# Fortuna-v21.net
KiCad netlist of a schematic drawn in EAGLE
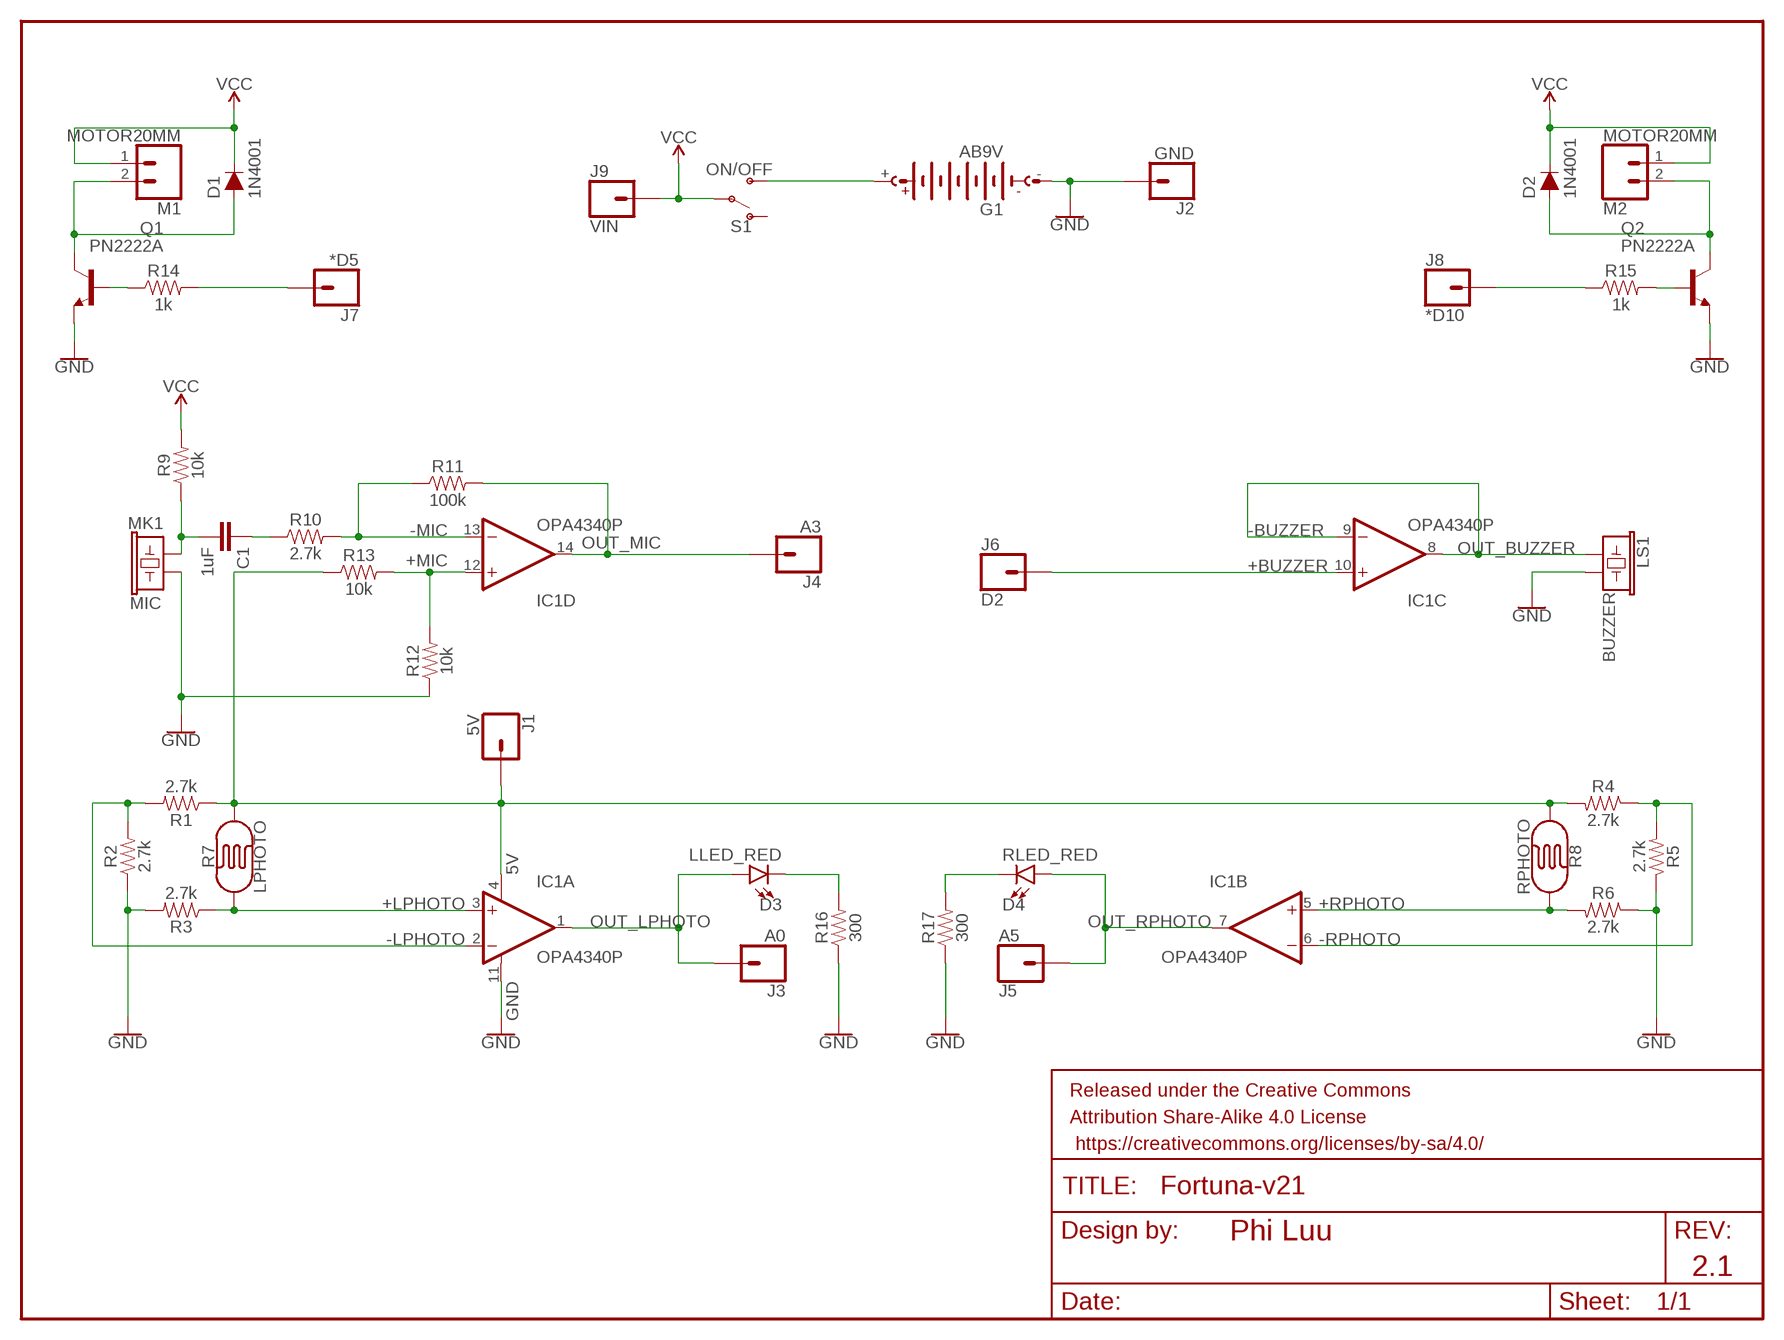
[diagram p0: schematic, sheet 1]

(export (version "E")
  (design (tool "Eeschema 10.0.6"))
  (components
    (comp (ref "C1")
      (value "1uF")
      (footprint "eagle-import:CAP-PTH-SMALL-KIT")
      (libsource (lib "eagle-import") (part "0.1UF-KIT-EZ-50V-20%"))
    )
    (comp (ref "D1")
      (value "1N4001")
      (footprint "eagle-import:DIODE-1N4001")
      (libsource (lib "eagle-import") (part "DIODE-PTH"))
    )
    (comp (ref "D2")
      (value "1N4001")
      (footprint "eagle-import:DIODE-1N4001")
      (libsource (lib "eagle-import") (part "DIODE-PTH"))
    )
    (comp (ref "D3")
      (value "LLED_RED")
      (footprint "eagle-import:LED_5MM")
      (libsource (lib "eagle-import") (part "LED5MM"))
    )
    (comp (ref "D4")
      (value "RLED_RED")
      (footprint "eagle-import:LED_5MM")
      (libsource (lib "eagle-import") (part "LED5MM"))
    )
    (comp (ref "FRAME1")
      (value "FRAME-LETTER")
      (footprint "eagle-import:CREATIVE_COMMONS")
      (libsource (lib "eagle-import") (part "FRAME-LETTER"))
    )
    (comp (ref "G1")
      (value "AB9V")
      (footprint "eagle-import:AB9V")
      (libsource (lib "eagle-import") (part "AB9V"))
    )
    (comp (ref "IC1")
      (value "OPA4340P")
      (footprint "eagle-import:DIL14")
      (libsource (lib "eagle-import") (part "OPA4340P"))
    )
    (comp (ref "J1")
      (value "5V")
      (footprint "eagle-import:1X01")
      (libsource (lib "eagle-import") (part "CONN_01"))
    )
    (comp (ref "J2")
      (value "GND")
      (footprint "eagle-import:1X01")
      (libsource (lib "eagle-import") (part "CONN_01"))
    )
    (comp (ref "J3")
      (value "A0")
      (footprint "eagle-import:1X01")
      (libsource (lib "eagle-import") (part "CONN_01"))
    )
    (comp (ref "J4")
      (value "A3")
      (footprint "eagle-import:1X01")
      (libsource (lib "eagle-import") (part "CONN_01"))
    )
    (comp (ref "J5")
      (value "A5")
      (footprint "eagle-import:1X01")
      (libsource (lib "eagle-import") (part "CONN_01"))
    )
    (comp (ref "J6")
      (value "D2")
      (footprint "eagle-import:1X01")
      (libsource (lib "eagle-import") (part "CONN_01"))
    )
    (comp (ref "J7")
      (value "*D5")
      (footprint "eagle-import:1X01")
      (libsource (lib "eagle-import") (part "CONN_01"))
    )
    (comp (ref "J8")
      (value "*D10")
      (footprint "eagle-import:1X01")
      (libsource (lib "eagle-import") (part "CONN_01"))
    )
    (comp (ref "J9")
      (value "VIN")
      (footprint "eagle-import:1X01")
      (libsource (lib "eagle-import") (part "CONN_01"))
    )
    (comp (ref "LS1")
      (value "BUZZER")
      (footprint "eagle-import:BUZZER-12MM")
      (libsource (lib "eagle-import") (part "BUZZER-PTH"))
    )
    (comp (ref "M1")
      (value "MOTOR20MM")
      (footprint "eagle-import:1X02")
      (libsource (lib "eagle-import") (part "CONN_02"))
    )
    (comp (ref "M2")
      (value "MOTOR20MM")
      (footprint "eagle-import:1X02")
      (libsource (lib "eagle-import") (part "CONN_02"))
    )
    (comp (ref "MK1")
      (value "MIC")
      (footprint "eagle-import:MICROPHONE-PTH-9.7MM")
      (libsource (lib "eagle-import") (part "MIC-PTH"))
    )
    (comp (ref "Q1")
      (value "PN2222A")
      (footprint "eagle-import:TO92-EBC-OVAL")
      (libsource (lib "eagle-import") (part "2N2222"))
    )
    (comp (ref "Q2")
      (value "PN2222A")
      (footprint "eagle-import:TO92-EBC-OVAL")
      (libsource (lib "eagle-import") (part "2N2222"))
    )
    (comp (ref "R1")
      (value "2.7k")
      (footprint "eagle-import:AXIAL-0.3")
      (libsource (lib "eagle-import") (part "1KOHM-HORIZ-1/4W-5%"))
    )
    (comp (ref "R2")
      (value "2.7k")
      (footprint "eagle-import:AXIAL-0.3")
      (libsource (lib "eagle-import") (part "1KOHM-HORIZ-1/4W-5%"))
    )
    (comp (ref "R3")
      (value "2.7k")
      (footprint "eagle-import:AXIAL-0.3")
      (libsource (lib "eagle-import") (part "1KOHM-HORIZ-1/4W-5%"))
    )
    (comp (ref "R4")
      (value "2.7k")
      (footprint "eagle-import:AXIAL-0.3")
      (libsource (lib "eagle-import") (part "1KOHM-HORIZ-1/4W-5%"))
    )
    (comp (ref "R5")
      (value "2.7k")
      (footprint "eagle-import:AXIAL-0.3")
      (libsource (lib "eagle-import") (part "1KOHM-HORIZ-1/4W-5%"))
    )
    (comp (ref "R6")
      (value "2.7k")
      (footprint "eagle-import:AXIAL-0.3")
      (libsource (lib "eagle-import") (part "1KOHM-HORIZ-1/4W-5%"))
    )
    (comp (ref "R7")
      (value "LPHOTO")
      (footprint "eagle-import:PHOTOCELL")
      (libsource (lib "eagle-import") (part "PHOTOCELLPTH"))
    )
    (comp (ref "R8")
      (value "RPHOTO")
      (footprint "eagle-import:PHOTOCELL")
      (libsource (lib "eagle-import") (part "PHOTOCELLPTH"))
    )
    (comp (ref "R9")
      (value "10k")
      (footprint "eagle-import:AXIAL-0.3")
      (libsource (lib "eagle-import") (part "1KOHM-HORIZ-1/4W-5%"))
    )
    (comp (ref "R10")
      (value "2.7k")
      (footprint "eagle-import:AXIAL-0.3")
      (libsource (lib "eagle-import") (part "1KOHM-HORIZ-1/4W-5%"))
    )
    (comp (ref "R11")
      (value "100k")
      (footprint "eagle-import:AXIAL-0.3")
      (libsource (lib "eagle-import") (part "1KOHM-HORIZ-1/4W-5%"))
    )
    (comp (ref "R12")
      (value "10k")
      (footprint "eagle-import:AXIAL-0.3")
      (libsource (lib "eagle-import") (part "1KOHM-HORIZ-1/4W-5%"))
    )
    (comp (ref "R13")
      (value "10k")
      (footprint "eagle-import:AXIAL-0.3")
      (libsource (lib "eagle-import") (part "1KOHM-HORIZ-1/4W-5%"))
    )
    (comp (ref "R14")
      (value "1k")
      (footprint "eagle-import:AXIAL-0.3")
      (libsource (lib "eagle-import") (part "1KOHM-HORIZ-1/4W-5%"))
    )
    (comp (ref "R15")
      (value "1k")
      (footprint "eagle-import:AXIAL-0.3")
      (libsource (lib "eagle-import") (part "1KOHM-HORIZ-1/4W-5%"))
    )
    (comp (ref "R16")
      (value "300")
      (footprint "eagle-import:AXIAL-0.3")
      (libsource (lib "eagle-import") (part "1KOHM-HORIZ-1/4W-5%"))
    )
    (comp (ref "R17")
      (value "300")
      (footprint "eagle-import:AXIAL-0.3")
      (libsource (lib "eagle-import") (part "1KOHM-HORIZ-1/4W-5%"))
    )
    (comp (ref "S1")
      (value "ON/OFF")
      (footprint "eagle-import:SWITCH_SPDT_PTH_11.6X4.0MM")
      (libsource (lib "eagle-import") (part "SWITCH-SPDT-PTH-11.6X4.0MM"))
    )
  )
  (nets
    (net (code "1") (name "/+LPHOTO") (class "Default")
      (node (ref "IC1") (pin "3") (pinfunction "+IN_3") (pintype "input"))
      (node (ref "R3") (pin "P$1") (pinfunction "1_P$1") (pintype "passive"))
      (node (ref "R7") (pin "1") (pinfunction "P$1_1") (pintype "bidirectional"))
    )
    (net (code "2") (name "/+MIC") (class "Default")
      (node (ref "IC1") (pin "12") (pinfunction "+IN_12") (pintype "input"))
      (node (ref "R12") (pin "P$2") (pinfunction "2_P$2") (pintype "passive"))
      (node (ref "R13") (pin "P$2") (pinfunction "2_P$2") (pintype "passive"))
    )
    (net (code "3") (name "/+RPHOTO") (class "Default")
      (node (ref "IC1") (pin "5") (pinfunction "+IN_5") (pintype "input"))
      (node (ref "R6") (pin "P$2") (pinfunction "2_P$2") (pintype "passive"))
      (node (ref "R8") (pin "1") (pinfunction "P$1_1") (pintype "bidirectional"))
    )
    (net (code "4") (name "/-LPHOTO") (class "Default")
      (node (ref "IC1") (pin "2") (pinfunction "-IN_2") (pintype "input"))
      (node (ref "R1") (pin "P$2") (pinfunction "2_P$2") (pintype "passive"))
      (node (ref "R2") (pin "P$2") (pinfunction "2_P$2") (pintype "passive"))
    )
    (net (code "5") (name "/-MIC") (class "Default")
      (node (ref "IC1") (pin "13") (pinfunction "-IN_13") (pintype "input"))
      (node (ref "R10") (pin "P$2") (pinfunction "2_P$2") (pintype "passive"))
      (node (ref "R11") (pin "P$1") (pinfunction "1_P$1") (pintype "passive"))
    )
    (net (code "6") (name "/-RPHOTO") (class "Default")
      (node (ref "IC1") (pin "6") (pinfunction "-IN_6") (pintype "input"))
      (node (ref "R4") (pin "P$1") (pinfunction "1_P$1") (pintype "passive"))
      (node (ref "R5") (pin "P$2") (pinfunction "2_P$2") (pintype "passive"))
    )
    (net (code "7") (name "/5V") (class "Default")
      (node (ref "IC1") (pin "4") (pinfunction "V+_4") (pintype "power_in"))
      (node (ref "J1") (pin "1") (pinfunction "1_1") (pintype "passive"))
      (node (ref "R1") (pin "P$1") (pinfunction "1_P$1") (pintype "passive"))
      (node (ref "R13") (pin "P$1") (pinfunction "1_P$1") (pintype "passive"))
      (node (ref "R4") (pin "P$2") (pinfunction "2_P$2") (pintype "passive"))
      (node (ref "R7") (pin "2") (pinfunction "P$2_2") (pintype "bidirectional"))
      (node (ref "R8") (pin "2") (pinfunction "P$2_2") (pintype "bidirectional"))
    )
    (net (code "8") (name "/OUT_BUZZER") (class "Default")
      (node (ref "IC1") (pin "8") (pinfunction "OUT_8") (pintype "output"))
      (node (ref "IC1") (pin "9") (pinfunction "-IN_9") (pintype "input"))
      (node (ref "LS1") (pin "+") (pinfunction "1_+") (pintype "passive"))
    )
    (net (code "9") (name "/OUT_LPHOTO") (class "Default")
      (node (ref "D3") (pin "A") (pinfunction "A_A") (pintype "passive"))
      (node (ref "IC1") (pin "1") (pinfunction "OUT_1") (pintype "output"))
      (node (ref "J3") (pin "1") (pinfunction "1_1") (pintype "passive"))
    )
    (net (code "10") (name "/OUT_MIC") (class "Default")
      (node (ref "IC1") (pin "14") (pinfunction "OUT_14") (pintype "output"))
      (node (ref "J4") (pin "1") (pinfunction "1_1") (pintype "passive"))
      (node (ref "R11") (pin "P$2") (pinfunction "2_P$2") (pintype "passive"))
    )
    (net (code "11") (name "/OUT_RPHOTO") (class "Default")
      (node (ref "D4") (pin "A") (pinfunction "A_A") (pintype "passive"))
      (node (ref "IC1") (pin "7") (pinfunction "OUT_7") (pintype "output"))
      (node (ref "J5") (pin "1") (pinfunction "1_1") (pintype "passive"))
    )
    (net (code "12") (name "GND") (class "Default")
      (node (ref "G1") (pin "-") (pinfunction "-_-") (pintype "passive"))
      (node (ref "IC1") (pin "11") (pinfunction "V-_11") (pintype "power_in"))
      (node (ref "J2") (pin "1") (pinfunction "1_1") (pintype "passive"))
      (node (ref "LS1") (pin "-") (pinfunction "2_-") (pintype "passive"))
      (node (ref "MK1") (pin "GND") (pinfunction "2_GND") (pintype "passive"))
      (node (ref "Q1") (pin "E") (pinfunction "E_E") (pintype "passive"))
      (node (ref "Q2") (pin "E") (pinfunction "E_E") (pintype "passive"))
      (node (ref "R12") (pin "P$1") (pinfunction "1_P$1") (pintype "passive"))
      (node (ref "R16") (pin "P$1") (pinfunction "1_P$1") (pintype "passive"))
      (node (ref "R17") (pin "P$1") (pinfunction "1_P$1") (pintype "passive"))
      (node (ref "R2") (pin "P$1") (pinfunction "1_P$1") (pintype "passive"))
      (node (ref "R3") (pin "P$2") (pinfunction "2_P$2") (pintype "passive"))
      (node (ref "R5") (pin "P$1") (pinfunction "1_P$1") (pintype "passive"))
      (node (ref "R6") (pin "P$1") (pinfunction "1_P$1") (pintype "passive"))
    )
    (net (code "13") (name "Net-(D1-PadA)") (class "Default")
      (node (ref "D1") (pin "A") (pinfunction "A_A") (pintype "passive"))
      (node (ref "M1") (pin "2") (pinfunction "2_2") (pintype "passive"))
      (node (ref "Q1") (pin "C") (pinfunction "C_C") (pintype "passive"))
    )
    (net (code "14") (name "Net-(D2-PadA)") (class "Default")
      (node (ref "D2") (pin "A") (pinfunction "A_A") (pintype "passive"))
      (node (ref "M2") (pin "2") (pinfunction "2_2") (pintype "passive"))
      (node (ref "Q2") (pin "C") (pinfunction "C_C") (pintype "passive"))
    )
    (net (code "15") (name "Net-(D3-C)") (class "Default")
      (node (ref "D3") (pin "K") (pinfunction "C_K") (pintype "passive"))
      (node (ref "R16") (pin "P$2") (pinfunction "2_P$2") (pintype "passive"))
    )
    (net (code "16") (name "Net-(D4-C)") (class "Default")
      (node (ref "D4") (pin "K") (pinfunction "C_K") (pintype "passive"))
      (node (ref "R17") (pin "P$2") (pinfunction "2_P$2") (pintype "passive"))
    )
    (net (code "17") (name "Net-(IC1C-+IN)") (class "Default")
      (node (ref "IC1") (pin "10") (pinfunction "+IN_10") (pintype "input"))
      (node (ref "J6") (pin "1") (pinfunction "1_1") (pintype "passive"))
    )
    (net (code "18") (name "Net-(MK1-1)") (class "Default")
      (node (ref "C1") (pin "2") (pinfunction "2_2") (pintype "passive"))
      (node (ref "MK1") (pin "OUT") (pinfunction "1_OUT") (pintype "passive"))
      (node (ref "R9") (pin "P$1") (pinfunction "1_P$1") (pintype "passive"))
    )
    (net (code "19") (name "Net-(R10-1)") (class "Default")
      (node (ref "C1") (pin "1") (pinfunction "1_1") (pintype "passive"))
      (node (ref "R10") (pin "P$1") (pinfunction "1_P$1") (pintype "passive"))
    )
    (net (code "20") (name "Net-(R14-1)") (class "Default")
      (node (ref "Q1") (pin "B") (pinfunction "B_B") (pintype "passive"))
      (node (ref "R14") (pin "P$1") (pinfunction "1_P$1") (pintype "passive"))
    )
    (net (code "21") (name "Net-(R14-2)") (class "Default")
      (node (ref "J7") (pin "1") (pinfunction "1_1") (pintype "passive"))
      (node (ref "R14") (pin "P$2") (pinfunction "2_P$2") (pintype "passive"))
    )
    (net (code "22") (name "Net-(R15-1)") (class "Default")
      (node (ref "J8") (pin "1") (pinfunction "1_1") (pintype "passive"))
      (node (ref "R15") (pin "P$1") (pinfunction "1_P$1") (pintype "passive"))
    )
    (net (code "23") (name "Net-(R15-2)") (class "Default")
      (node (ref "Q2") (pin "B") (pinfunction "B_B") (pintype "passive"))
      (node (ref "R15") (pin "P$2") (pinfunction "2_P$2") (pintype "passive"))
    )
    (net (code "24") (name "Net-(S1-S)") (class "Default")
      (node (ref "G1") (pin "+") (pinfunction "+_+") (pintype "passive"))
      (node (ref "S1") (pin "3") (pinfunction "S_3") (pintype "passive"))
    )
    (net (code "25") (name "VCC") (class "Default")
      (node (ref "D1") (pin "C") (pinfunction "C_C") (pintype "passive"))
      (node (ref "D2") (pin "C") (pinfunction "C_C") (pintype "passive"))
      (node (ref "J9") (pin "1") (pinfunction "1_1") (pintype "passive"))
      (node (ref "M1") (pin "1") (pinfunction "1_1") (pintype "passive"))
      (node (ref "M2") (pin "1") (pinfunction "1_1") (pintype "passive"))
      (node (ref "R9") (pin "P$2") (pinfunction "2_P$2") (pintype "passive"))
      (node (ref "S1") (pin "2") (pinfunction "P_2") (pintype "passive"))
    )
    (net (code "26") (name "unconnected-(S1-O-Pad1)") (class "Default")
      (node (ref "S1") (pin "1") (pinfunction "O_1") (pintype "passive"))
    )
  )
)
